# Power_Distribution_-_Low_Current_Load_Dr.net
KiCad netlist of a schematic drawn in Altium Designer
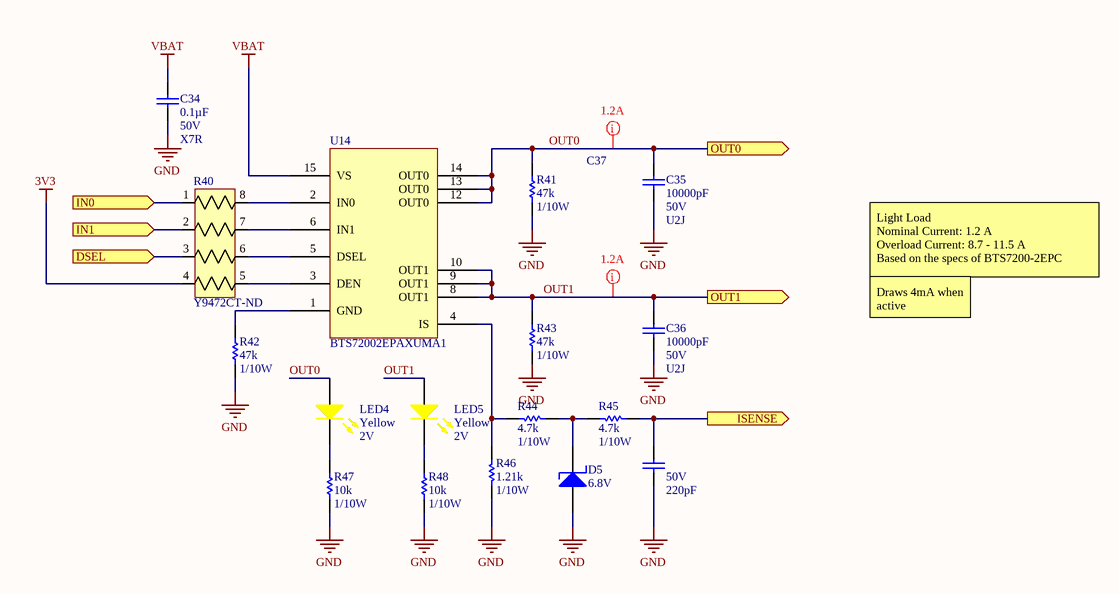
[diagram p0: Power Distribution - Low Current Load Driver.SchDoc]

(export (version "E")
  (design (tool "Eeschema 10.0.6"))
  (components
    (comp (ref "C34")
      (value "CAP CER 0.1UF 50V 10% X7R 0603")
      (footprint "CAP, 0603")
      (description "0.10µF ±10% 50V Ceramic Capacitor X7R 0603 (1608 Metric)")
      (fields
        (field (name "TOLERANCE") "±10%")
        (field (name "CAPACITANCE") "0.1µF")
        (field (name "VOLTAGE") "50V")
        (field (name "TEMPERATURE COEFFICIENT") "X7R")
      )
      (libsource (lib "Schematic Diagrams") (part "CAP CER 0.1UF 50V 10% X7R 0603"))
    )
    (comp (ref "C35")
      (value "CAP CER 10nF 50V 5% X7R 0603")
      (footprint "CAP, 0603")
      (description "10000pF ±5% 50V Ceramic Capacitor U2J 0603 (1608 Metric)")
      (fields
        (field (name "TOLERANCE") "±5%")
        (field (name "CAPACITANCE") "10000pF")
        (field (name "VOLTAGE") "50V")
        (field (name "TEMPERATURE COEFFICIENT") "U2J")
      )
      (libsource (lib "Schematic Diagrams") (part "CAP CER 10nF 50V 5% X7R 0603"))
    )
    (comp (ref "C36")
      (value "CAP CER 10nF 50V 5% X7R 0603")
      (footprint "CAP, 0603")
      (description "10000pF ±5% 50V Ceramic Capacitor U2J 0603 (1608 Metric)")
      (fields
        (field (name "TOLERANCE") "±5%")
        (field (name "CAPACITANCE") "10000pF")
        (field (name "VOLTAGE") "50V")
        (field (name "TEMPERATURE COEFFICIENT") "U2J")
      )
      (libsource (lib "Schematic Diagrams") (part "CAP CER 10nF 50V 5% X7R 0603"))
    )
    (comp (ref "C37")
      (value "CAP CER 220PF 50V C0G/NP0 0603")
      (footprint "CAP, 0603")
      (description "220pF ±5% 50V Ceramic Capacitor C0G, NP0 0603 (1608 Metric)")
      (fields
        (field (name "MANUFACTURER") "KEMET")
        (field (name "TOLERANCE") "5%")
        (field (name "VOLTAGE RATING") "50V")
        (field (name "CAPACITANCE") "220pF")
      )
      (libsource (lib "Schematic Diagrams") (part "CAP CER 220PF 50V C0G/NP0 0603"))
    )
    (comp (ref "D5")
      (value "6.8V")
      (footprint "DIODE SOD123")
      (description "Zener Diode 6.8V 500mW ±5% Surface Mount SOD-123")
      (fields (field (name "MANUFACTURER") "Diodes Incorporated") (field (name "TOLERANCE") "±5%"))
      (libsource (lib "Schematic Diagrams") (part "DIODE ZENER 6.8V 500MW SOD123"))
    )
    (comp (ref "LED4")
      (value "LED YELLOW CLEAR 2.1V 0603")
      (footprint "LED_0603")
      (description "Yellow 590nm LED Indication - Discrete 2V 0603 (1608 Metric)")
      (fields
        (field (name "MANUFACTURER") "Wurth Electronics Inc.")
        (field (name "MANUFACTURER PART NUMBER") "150060YS75000")
        (field (name "COLOR") "Yellow")
        (field (name "VOLTAGE - FORWARD (VF) (TYP)") "2V")
      )
      (libsource (lib "Schematic Diagrams") (part "LED YELLOW CLEAR 2.1V 0603"))
    )
    (comp (ref "LED5")
      (value "LED YELLOW CLEAR 2.1V 0603")
      (footprint "LED_0603")
      (description "Yellow 590nm LED Indication - Discrete 2V 0603 (1608 Metric)")
      (fields
        (field (name "MANUFACTURER") "Wurth Electronics Inc.")
        (field (name "MANUFACTURER PART NUMBER") "150060YS75000")
        (field (name "COLOR") "Yellow")
        (field (name "VOLTAGE - FORWARD (VF) (TYP)") "2V")
      )
      (libsource (lib "Schematic Diagrams") (part "LED YELLOW CLEAR 2.1V 0603"))
    )
    (comp (ref "R40")
      (value "RES ARRAY 4 RES 4.7K OHM 1206")
      (footprint "RES ARRAY 4RES 1206")
      (fields (field (name "TOLERANCE") "±5%") (field (name "SUPPLIER PART NUMBER 1") "Y9472CT-ND"))
      (libsource (lib "Schematic Diagrams") (part "RES ARRAY 4 RES 4.7K OHM 1206"))
    )
    (comp (ref "R41")
      (value "RES 47K OHM 1% 1/10W 0603")
      (footprint "RES, 0603")
      (description "47 kOhms ±1% 0.1W, 1/10W Chip Resistor 0603 (1608 Metric) Automotive AEC-Q200 Thick Film")
      (fields
        (field (name "MANUFACTURER") "Panasonic")
        (field (name "MANUFACTURER PART NUMBER") "ERJ3EKF4702V")
        (field (name "RESISTANCE") "47k")
        (field (name "POWER RATING") "1/10W")
      )
      (libsource (lib "Schematic Diagrams") (part "RES 47K OHM 1% 1/10W 0603"))
    )
    (comp (ref "R42")
      (value "RES 47K OHM 1% 1/10W 0603")
      (footprint "RES, 0603")
      (description "47 kOhms ±1% 0.1W, 1/10W Chip Resistor 0603 (1608 Metric) Automotive AEC-Q200 Thick Film")
      (fields
        (field (name "MANUFACTURER") "Panasonic")
        (field (name "MANUFACTURER PART NUMBER") "ERJ3EKF4702V")
        (field (name "RESISTANCE") "47k")
        (field (name "POWER RATING") "1/10W")
      )
      (libsource (lib "Schematic Diagrams") (part "RES 47K OHM 1% 1/10W 0603"))
    )
    (comp (ref "R43")
      (value "RES 47K OHM 1% 1/10W 0603")
      (footprint "RES, 0603")
      (description "47 kOhms ±1% 0.1W, 1/10W Chip Resistor 0603 (1608 Metric) Automotive AEC-Q200 Thick Film")
      (fields
        (field (name "MANUFACTURER") "Panasonic")
        (field (name "MANUFACTURER PART NUMBER") "ERJ3EKF4702V")
        (field (name "RESISTANCE") "47k")
        (field (name "POWER RATING") "1/10W")
      )
      (libsource (lib "Schematic Diagrams") (part "RES 47K OHM 1% 1/10W 0603"))
    )
    (comp (ref "R44")
      (value "RES 4.7K OHM 1% 1/10W 0603")
      (footprint "RES, 0603")
      (description "4.7k Ohm ±1% 0.1W, 1/10W Chip Resistor 0603 (1608 Metric) Moisture Resistant Thick Film")
      (fields
        (field (name "TOLERANCE") "±1%")
        (field (name "RESISTANCE (OHMS)") "4.7k")
        (field (name "POWER (WATTS)") "1/10W")
      )
      (libsource (lib "Schematic Diagrams") (part "RES 4.7K OHM 1% 1/10W 0603"))
    )
    (comp (ref "R45")
      (value "RES 4.7K OHM 1% 1/10W 0603")
      (footprint "RES, 0603")
      (description "4.7k Ohm ±1% 0.1W, 1/10W Chip Resistor 0603 (1608 Metric) Moisture Resistant Thick Film")
      (fields
        (field (name "TOLERANCE") "±1%")
        (field (name "RESISTANCE (OHMS)") "4.7k")
        (field (name "POWER (WATTS)") "1/10W")
      )
      (libsource (lib "Schematic Diagrams") (part "RES 4.7K OHM 1% 1/10W 0603"))
    )
    (comp (ref "R46")
      (value "RES 1.21K OHM 1% 1/10W 0603")
      (footprint "RES, 0603")
      (description "1.21k Ohm ±1% 0.1W, 1/10W Chip Resistor 0603 (1608 Metric) Moisture Resistant Thick Film")
      (fields
        (field (name "TOLERANCE") "±1%")
        (field (name "RESISTANCE") "1.21k")
        (field (name "POWER") "1/10W")
      )
      (libsource (lib "Schematic Diagrams") (part "RES 1.21K OHM 1% 1/10W 0603"))
    )
    (comp (ref "R47")
      (value "RES 10K OHM 1% 1/10W 0603")
      (footprint "RES, 0603")
      (description "RES SMD 10K OHM 1% 1/10W 0603")
      (fields
        (field (name "TOLERANCE") "±1%")
        (field (name "RESISTANCE") "10k")
        (field (name "POWER") "1/10W")
      )
      (libsource (lib "Schematic Diagrams") (part "RES 10K OHM 1% 1/10W 0603"))
    )
    (comp (ref "R48")
      (value "RES 10K OHM 1% 1/10W 0603")
      (footprint "RES, 0603")
      (description "RES SMD 10K OHM 1% 1/10W 0603")
      (fields
        (field (name "TOLERANCE") "±1%")
        (field (name "RESISTANCE") "10k")
        (field (name "POWER") "1/10W")
      )
      (libsource (lib "Schematic Diagrams") (part "RES 10K OHM 1% 1/10W 0603"))
    )
    (comp (ref "U14")
      (value "IC LOAD SWITCH BTS7200-2EPA PG-TSDSO-14")
      (footprint "IC LOAD SWITCH PG-TSDSO-14-22")
      (description "Power Switch/Driver 1:1 N-Channel 1.2A PG-TSDSO-14-22")
      (fields
        (field (name "MANUFACTURER") "Infineon")
        (field (name "MANUFACTURER PART NUMBER") "BTS72002EPAXUMA1")
      )
      (libsource (lib "Schematic Diagrams") (part "IC LOAD SWITCH BTS7200-2EPA PG-TSDSO-14"))
    )
  )
  (nets
    (net (code "1") (name "/DSEL") (class "Default")
      (node (ref "R40") (pin "3") (pinfunction "3_3") (pintype "passive"))
    )
    (net (code "2") (name "/IN0") (class "Default")
      (node (ref "R40") (pin "1") (pinfunction "1_1") (pintype "passive"))
    )
    (net (code "3") (name "/IN1") (class "Default")
      (node (ref "R40") (pin "2") (pinfunction "2_2") (pintype "passive"))
    )
    (net (code "4") (name "/ISENSE") (class "Default")
      (node (ref "C37") (pin "1") (pinfunction "1_1") (pintype "passive"))
      (node (ref "R45") (pin "1") (pinfunction "1_1") (pintype "passive"))
    )
    (net (code "5") (name "/OUT0") (class "Default")
      (node (ref "C35") (pin "1") (pinfunction "1_1") (pintype "passive"))
      (node (ref "LED4") (pin "1") (pinfunction "A_1") (pintype "passive"))
      (node (ref "R41") (pin "1") (pinfunction "1_1") (pintype "passive"))
      (node (ref "U14") (pin "12") (pinfunction "OUT0_12") (pintype "passive"))
      (node (ref "U14") (pin "13") (pinfunction "OUT0_13") (pintype "passive"))
      (node (ref "U14") (pin "14") (pinfunction "OUT0_14") (pintype "passive"))
    )
    (net (code "6") (name "/OUT1") (class "Default")
      (node (ref "C36") (pin "1") (pinfunction "1_1") (pintype "passive"))
      (node (ref "LED5") (pin "1") (pinfunction "A_1") (pintype "passive"))
      (node (ref "R43") (pin "1") (pinfunction "1_1") (pintype "passive"))
      (node (ref "U14") (pin "10") (pinfunction "OUT1_10") (pintype "passive"))
      (node (ref "U14") (pin "8") (pinfunction "OUT1_8") (pintype "passive"))
      (node (ref "U14") (pin "9") (pinfunction "OUT1_9") (pintype "passive"))
    )
    (net (code "7") (name "3V3") (class "Default")
      (node (ref "R40") (pin "4") (pinfunction "4_4") (pintype "passive"))
    )
    (net (code "8") (name "GND") (class "Default")
      (node (ref "C34") (pin "2") (pinfunction "2_2") (pintype "passive"))
      (node (ref "C35") (pin "2") (pinfunction "2_2") (pintype "passive"))
      (node (ref "C36") (pin "2") (pinfunction "2_2") (pintype "passive"))
      (node (ref "C37") (pin "2") (pinfunction "2_2") (pintype "passive"))
      (node (ref "D5") (pin "2") (pinfunction "A_2") (pintype "passive"))
      (node (ref "R41") (pin "2") (pinfunction "2_2") (pintype "passive"))
      (node (ref "R42") (pin "2") (pinfunction "2_2") (pintype "passive"))
      (node (ref "R43") (pin "2") (pinfunction "2_2") (pintype "passive"))
      (node (ref "R46") (pin "2") (pinfunction "2_2") (pintype "passive"))
      (node (ref "R47") (pin "2") (pinfunction "2_2") (pintype "passive"))
      (node (ref "R48") (pin "2") (pinfunction "2_2") (pintype "passive"))
    )
    (net (code "9") (name "Net-(D5-K)") (class "Default")
      (node (ref "D5") (pin "1") (pinfunction "K_1") (pintype "passive"))
      (node (ref "R44") (pin "1") (pinfunction "1_1") (pintype "passive"))
      (node (ref "R45") (pin "2") (pinfunction "2_2") (pintype "passive"))
    )
    (net (code "10") (name "Net-(LED4-K)") (class "Default")
      (node (ref "LED4") (pin "2") (pinfunction "K_2") (pintype "passive"))
      (node (ref "R47") (pin "1") (pinfunction "1_1") (pintype "passive"))
    )
    (net (code "11") (name "Net-(LED5-K)") (class "Default")
      (node (ref "LED5") (pin "2") (pinfunction "K_2") (pintype "passive"))
      (node (ref "R48") (pin "1") (pinfunction "1_1") (pintype "passive"))
    )
    (net (code "12") (name "Net-(U14-DEN)") (class "Default")
      (node (ref "R40") (pin "5") (pinfunction "5_5") (pintype "passive"))
      (node (ref "U14") (pin "3") (pinfunction "DEN_3") (pintype "passive"))
    )
    (net (code "13") (name "Net-(U14-DSEL)") (class "Default")
      (node (ref "R40") (pin "6") (pinfunction "6_6") (pintype "passive"))
      (node (ref "U14") (pin "5") (pinfunction "DSEL_5") (pintype "passive"))
    )
    (net (code "14") (name "Net-(U14-GND)") (class "Default")
      (node (ref "R42") (pin "1") (pinfunction "1_1") (pintype "passive"))
      (node (ref "U14") (pin "1") (pinfunction "GND_1") (pintype "passive"))
    )
    (net (code "15") (name "Net-(U14-IN0)") (class "Default")
      (node (ref "R40") (pin "8") (pinfunction "8_8") (pintype "passive"))
      (node (ref "U14") (pin "2") (pinfunction "IN0_2") (pintype "passive"))
    )
    (net (code "16") (name "Net-(U14-IN1)") (class "Default")
      (node (ref "R40") (pin "7") (pinfunction "7_7") (pintype "passive"))
      (node (ref "U14") (pin "6") (pinfunction "IN1_6") (pintype "passive"))
    )
    (net (code "17") (name "Net-(U14-IS)") (class "Default")
      (node (ref "R44") (pin "2") (pinfunction "2_2") (pintype "passive"))
      (node (ref "R46") (pin "1") (pinfunction "1_1") (pintype "passive"))
      (node (ref "U14") (pin "4") (pinfunction "IS_4") (pintype "passive"))
    )
    (net (code "18") (name "VBAT") (class "Default")
      (node (ref "C34") (pin "1") (pinfunction "1_1") (pintype "passive"))
      (node (ref "U14") (pin "15") (pinfunction "VS_15") (pintype "passive"))
    )
  )
)
